# 36V_Supply.net
KiCad netlist of a schematic drawn in Altium Designer
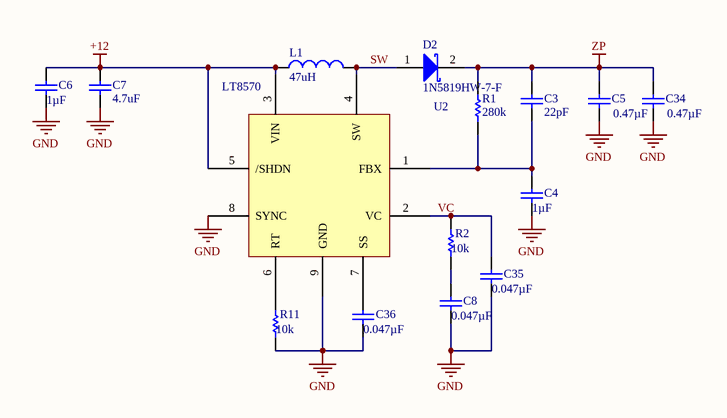
[diagram p0: 36V_Supply.SchDoc]

(export (version "E")
  (design (tool "Eeschema 10.0.6"))
  (components
    (comp (ref "C3")
      (value "22pF")
      (footprint "CAPC1206(3216)170_L")
      (description "CAP CER 22PF 50V C0G/NP0 1206")
      (fields
        (field (name "MANUFACTURER") "KEMET")
        (field (name "MANUFACTURER PART NUMBER") "C1206C220K5GACTU")
      )
      (libsource (lib "Altium Content Vault") (part "CMP-1037-04573-1"))
    )
    (comp (ref "C4")
      (value "CAP CER 1UF 50V X7R 1210")
      (footprint "CAPC1210(3225)100_N")
      (fields
        (field (name "MANUFACTURER") "Taiyo Yuden")
        (field (name "MANUFACTURER PART NUMBER") "UMK325B7105KH-T")
        (field (name "CAPACITANCE") "1µF")
        (field (name "TOLERANCE") "±10%")
      )
      (libsource (lib "Altium Content Vault") (part "CMP-1038-01123-1"))
    )
    (comp (ref "C5")
      (value "CAP CER 0.47UF 50V X7R 1206")
      (footprint "CAPC1206(3216)190_N")
      (fields
        (field (name "MANUFACTURER") "Taiyo Yuden")
        (field (name "MANUFACTURER PART NUMBER") "UMK316B7474KL-T")
        (field (name "CAPACITANCE") "0.47µF")
        (field (name "TOLERANCE") "±10%")
      )
      (libsource (lib "Altium Content Vault") (part "CMP-1037-04570-1"))
    )
    (comp (ref "C6")
      (value "CAP CER 1UF 16V X7R 0805")
      (footprint "CAPC0805(2012)145_N")
      (fields
        (field (name "MANUFACTURER") "Taiyo Yuden")
        (field (name "MANUFACTURER PART NUMBER") "EMK212B7105KG-T")
        (field (name "CAPACITANCE") "1µF")
        (field (name "TOLERANCE") "±10%")
      )
      (libsource (lib "Altium Content Vault") (part "CMP-1036-04795-1"))
    )
    (comp (ref "C7")
      (value "4.7uF")
      (footprint "CAPC0805(2012)145_M")
      (description "CAP CER 4.7UF 16V X7R 0805")
      (fields
        (field (name "MANUFACTURER") "KEMET")
        (field (name "MANUFACTURER PART NUMBER") "C0805C475K4RACTU")
      )
      (libsource (lib "Altium Content Vault") (part "CMP-1036-04750-1"))
    )
    (comp (ref "C8")
      (value "CAP CER 0.047UF 16V X7R 0603")
      (footprint "CAPC0805(2012)145_N")
      (fields
        (field (name "MANUFACTURER") "Murata Electronics North America")
        (field (name "MANUFACTURER PART NUMBER") "GRM188R71C473KA01D")
        (field (name "CAPACITANCE") "0.047µF")
        (field (name "TOLERANCE") "±10%")
      )
      (libsource (lib "Altium Content Vault") (part "CMP-1036-04795-1"))
    )
    (comp (ref "C34")
      (value "CAP CER 0.47UF 50V X7R 1206")
      (footprint "CAPC1206(3216)190_N")
      (fields
        (field (name "MANUFACTURER") "Taiyo Yuden")
        (field (name "MANUFACTURER PART NUMBER") "UMK316B7474KL-T")
        (field (name "CAPACITANCE") "0.47µF")
        (field (name "TOLERANCE") "±10%")
      )
      (libsource (lib "Altium Content Vault") (part "CMP-1037-04570-1"))
    )
    (comp (ref "C35")
      (value "CAP CER 0.047UF 16V X7R 0603")
      (footprint "CAPC0805(2012)145_N")
      (fields
        (field (name "MANUFACTURER") "Murata Electronics North America")
        (field (name "MANUFACTURER PART NUMBER") "GRM188R71C473KA01D")
        (field (name "CAPACITANCE") "0.047µF")
        (field (name "TOLERANCE") "±10%")
      )
      (libsource (lib "Altium Content Vault") (part "CMP-1036-04795-1"))
    )
    (comp (ref "C36")
      (value "CAP CER 0.047UF 16V X7R 0603")
      (footprint "CAPC0805(2012)145_N")
      (fields
        (field (name "MANUFACTURER") "Murata Electronics North America")
        (field (name "MANUFACTURER PART NUMBER") "GRM188R71C473KA01D")
        (field (name "CAPACITANCE") "0.047µF")
        (field (name "TOLERANCE") "±10%")
      )
      (libsource (lib "Altium Content Vault") (part "CMP-1036-04795-1"))
    )
    (comp (ref "D2")
      (value "1N5819HW-7-F")
      (footprint "DIOD-SOD-123-2_V")
      (fields (field (name "MANUFACTURER") "Diodes Inc"))
      (libsource (lib "Altium Content Vault") (part "DIOD-DSKY-A1K2-2"))
    )
    (comp (ref "L1")
      (value "47uH")
      (footprint "C1210")
      (description "FIXED IND 47UH 170MA 1.3 OHM SMD")
      (fields
        (field (name "MANUFACTURER") "Murata Electronics North America")
        (field (name "MANUFACTURER PART NUMBER") "LQH32CN470K23L")
      )
      (libsource (lib "Miscellaneous Devices") (part "Inductor"))
    )
    (comp (ref "R1")
      (value "RES SMD 280K OHM 1% 1/8W 0805")
      (footprint "RESC0805(2012)_M")
      (fields
        (field (name "MANUFACTURER") "Vishay Dale")
        (field (name "MANUFACTURER PART NUMBER") "CRCW0805280KFKEA")
        (field (name "RESISTANCE (OHMS)") "280k")
        (field (name "TOLERANCE") "±1%")
      )
      (libsource (lib "Altium Content Vault") (part "CMP-1013-00017-1"))
    )
    (comp (ref "R2")
      (value "RES SMD 10K OHM 1% 1/8W 0805")
      (footprint "RESC0805(2012)_M")
      (fields
        (field (name "MANUFACTURER") "Yageo")
        (field (name "MANUFACTURER PART NUMBER") "RC0805FR-0710KL")
        (field (name "RESISTANCE (OHMS)") "10k")
        (field (name "TOLERANCE") "±1%")
      )
      (libsource (lib "Altium Content Vault") (part "CMP-1013-00017-1"))
    )
    (comp (ref "R11")
      (value "RES SMD 10K OHM 1% 1/8W 0805")
      (footprint "RESC0805(2012)_M")
      (fields
        (field (name "MANUFACTURER") "Yageo")
        (field (name "MANUFACTURER PART NUMBER") "RC0805FR-0710KL")
        (field (name "RESISTANCE (OHMS)") "10k")
        (field (name "TOLERANCE") "±1%")
      )
      (libsource (lib "Altium Content Vault") (part "CMP-1013-00017-1"))
    )
    (comp (ref "U2")
      (value "LT8570")
      (footprint "LT8570-MSOP")
      (description "IC REG MULT CONFIG INV ADJ 8MSOP")
      (fields
        (field (name "MANUFACTURER") "Analog Devices / Linear Technology")
        (field (name "MANUFACTURER PART NUMBER") "LT8570EMS8E#TRPBF")
      )
      (libsource (lib "ZLS_Schematic_lib") (part "LT8570"))
    )
  )
  (nets
    (net (code "1") (name "+12") (class "Default")
      (node (ref "C6") (pin "2") (pinfunction "2_2") (pintype "passive"))
      (node (ref "C7") (pin "2") (pinfunction "2_2") (pintype "passive"))
      (node (ref "L1") (pin "1") (pinfunction "1_1") (pintype "passive"))
      (node (ref "U2") (pin "3") (pinfunction "VIN_3") (pintype "passive"))
      (node (ref "U2") (pin "5") (pinfunction "/SHDN_5") (pintype "passive"))
    )
    (net (code "2") (name "/SW") (class "Default")
      (node (ref "D2") (pin "1") (pinfunction "A_1") (pintype "passive"))
      (node (ref "L1") (pin "2") (pinfunction "2_2") (pintype "passive"))
      (node (ref "U2") (pin "4") (pinfunction "SW_4") (pintype "passive"))
    )
    (net (code "3") (name "/VC") (class "Default")
      (node (ref "C35") (pin "2") (pinfunction "2_2") (pintype "passive"))
      (node (ref "R2") (pin "1") (pinfunction "1_1") (pintype "passive"))
      (node (ref "U2") (pin "2") (pinfunction "VC_2") (pintype "passive"))
    )
    (net (code "4") (name "GND") (class "Default")
      (node (ref "C34") (pin "1") (pinfunction "1_1") (pintype "passive"))
      (node (ref "C35") (pin "1") (pinfunction "1_1") (pintype "passive"))
      (node (ref "C36") (pin "1") (pinfunction "1_1") (pintype "passive"))
      (node (ref "C4") (pin "1") (pinfunction "1_1") (pintype "passive"))
      (node (ref "C5") (pin "1") (pinfunction "1_1") (pintype "passive"))
      (node (ref "C6") (pin "1") (pinfunction "1_1") (pintype "passive"))
      (node (ref "C7") (pin "1") (pinfunction "1_1") (pintype "passive"))
      (node (ref "C8") (pin "1") (pinfunction "1_1") (pintype "passive"))
      (node (ref "R11") (pin "2") (pinfunction "2_2") (pintype "passive"))
      (node (ref "U2") (pin "8") (pinfunction "SYNC_8") (pintype "passive"))
      (node (ref "U2") (pin "9") (pinfunction "GND_9") (pintype "passive"))
    )
    (net (code "5") (name "Net-(C8-Pad2)") (class "Default")
      (node (ref "C8") (pin "2") (pinfunction "2_2") (pintype "passive"))
      (node (ref "R2") (pin "2") (pinfunction "2_2") (pintype "passive"))
    )
    (net (code "6") (name "Net-(U2-FBX)") (class "Default")
      (node (ref "C3") (pin "1") (pinfunction "1_1") (pintype "passive"))
      (node (ref "C4") (pin "2") (pinfunction "2_2") (pintype "passive"))
      (node (ref "R1") (pin "2") (pinfunction "2_2") (pintype "passive"))
      (node (ref "U2") (pin "1") (pinfunction "FBX_1") (pintype "passive"))
    )
    (net (code "7") (name "Net-(U2-RT)") (class "Default")
      (node (ref "R11") (pin "1") (pinfunction "1_1") (pintype "passive"))
      (node (ref "U2") (pin "6") (pinfunction "RT_6") (pintype "passive"))
    )
    (net (code "8") (name "Net-(U2-SS)") (class "Default")
      (node (ref "C36") (pin "2") (pinfunction "2_2") (pintype "passive"))
      (node (ref "U2") (pin "7") (pinfunction "SS_7") (pintype "passive"))
    )
    (net (code "9") (name "ZP") (class "Default")
      (node (ref "C3") (pin "2") (pinfunction "2_2") (pintype "passive"))
      (node (ref "C34") (pin "2") (pinfunction "2_2") (pintype "passive"))
      (node (ref "C5") (pin "2") (pinfunction "2_2") (pintype "passive"))
      (node (ref "D2") (pin "2") (pinfunction "K_2") (pintype "passive"))
      (node (ref "R1") (pin "1") (pinfunction "1_1") (pintype "passive"))
    )
  )
)
